# schematics.net
KiCad netlist of a schematic drawn in EAGLE
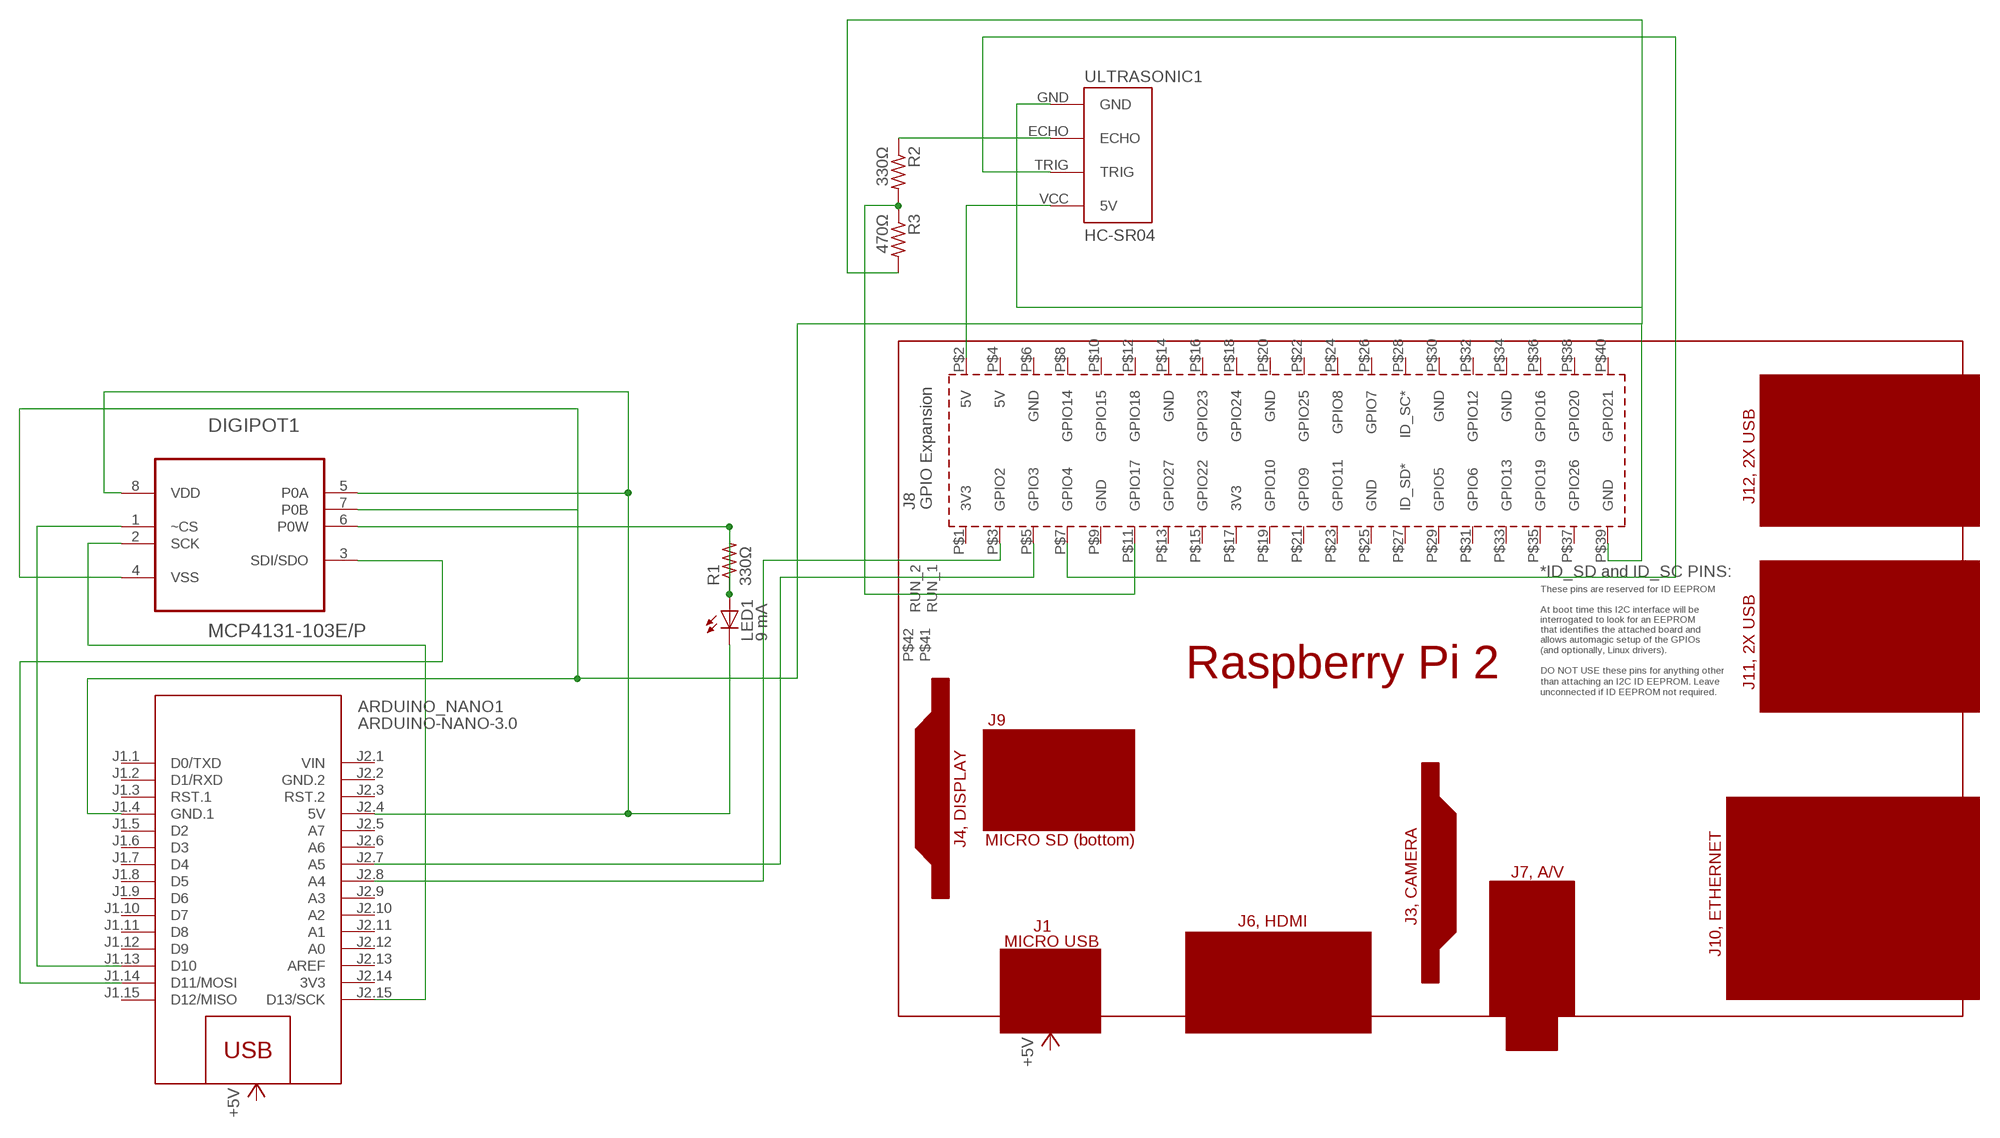
[diagram p0: schematic, sheet 1]

(export (version "E")
  (design (tool "Eeschema 10.0.6"))
  (components
    (comp (ref "ARDUINO_NANO1")
      (value "ARDUINO-NANO-3.0")
      (footprint "eagle-import:ARDUINO-NANO-3.0")
      (libsource (lib "eagle-import") (part "ARDUINO-NANO-3.0"))
    )
    (comp (ref "DIGIPOT1")
      (value "MCP4131-103E/P")
      (footprint "eagle-import:DIP254P762X533-8")
      (libsource (lib "eagle-import") (part "MCP4131-103E/P"))
    )
    (comp (ref "LED1")
      (value "9 mA")
      (footprint "eagle-import:SMARTLED-TTW")
      (libsource (lib "eagle-import") (part "LED"))
    )
    (comp (ref "R1")
      (value "330Ω")
      (footprint "eagle-import:0207_10")
      (libsource (lib "eagle-import") (part "R-US_0207/10"))
    )
    (comp (ref "R2")
      (value "330Ω")
      (footprint "eagle-import:0204_7")
      (libsource (lib "eagle-import") (part "R-US_0204/7"))
    )
    (comp (ref "R3")
      (value "470Ω")
      (footprint "eagle-import:0204_7")
      (libsource (lib "eagle-import") (part "R-US_0204/7"))
    )
    (comp (ref "RASPBERRY_PI_TWO1")
      (value "RPI2")
      (footprint "eagle-import:RPI2")
      (libsource (lib "eagle-import") (part "RPI2"))
    )
    (comp (ref "ULTRASONIC1")
      (value "HC-SR04")
      (footprint "eagle-import:HC-SR04_FOOTPRINT")
      (libsource (lib "eagle-import") (part "HC-SR04"))
    )
  )
  (nets
    (net (code "2") (name "/3V3") (class "Default")
      (node (ref "ARDUINO_NANO1") (pin "J2.14") (pinfunction "3V3_J2.14") (pintype "power_in"))
    )
    (net (code "3") (name "/GND.2") (class "Default")
      (node (ref "ARDUINO_NANO1") (pin "J2.2") (pinfunction "GND.2_J2.2") (pintype "power_in"))
    )
    (net (code "4") (name "/VIN") (class "Default")
      (node (ref "ARDUINO_NANO1") (pin "J2.1") (pinfunction "VIN_J2.1") (pintype "power_in"))
    )
    (net (code "5") (name "Net-(ARDUINO_NANO1-5V)") (class "Default")
      (node (ref "ARDUINO_NANO1") (pin "J2.4") (pinfunction "5V_J2.4") (pintype "power_in"))
      (node (ref "DIGIPOT1") (pin "5") (pinfunction "P0A_5") (pintype "bidirectional"))
      (node (ref "DIGIPOT1") (pin "8") (pinfunction "VDD_8") (pintype "power_in"))
      (node (ref "LED1") (pin "C@1") (pinfunction "C_C@1") (pintype "passive"))
    )
    (net (code "6") (name "Net-(ARDUINO_NANO1-A4)") (class "Default")
      (node (ref "ARDUINO_NANO1") (pin "J2.8") (pinfunction "A4_J2.8") (pintype "bidirectional"))
      (node (ref "RASPBERRY_PI_TWO1") (pin "P$3") (pinfunction "GPIO2_P$3") (pintype "bidirectional"))
    )
    (net (code "7") (name "Net-(ARDUINO_NANO1-A5)") (class "Default")
      (node (ref "ARDUINO_NANO1") (pin "J2.7") (pinfunction "A5_J2.7") (pintype "bidirectional"))
      (node (ref "RASPBERRY_PI_TWO1") (pin "P$5") (pinfunction "GPIO3_P$5") (pintype "bidirectional"))
    )
    (net (code "8") (name "Net-(ARDUINO_NANO1-D10)") (class "Default")
      (node (ref "ARDUINO_NANO1") (pin "J1.13") (pinfunction "D10_J1.13") (pintype "bidirectional"))
      (node (ref "DIGIPOT1") (pin "1") (pinfunction "~{CS}_1") (pintype "input"))
    )
    (net (code "9") (name "Net-(ARDUINO_NANO1-D11{slash}MOSI)") (class "Default")
      (node (ref "ARDUINO_NANO1") (pin "J1.14") (pinfunction "D11/MOSI_J1.14") (pintype "bidirectional"))
      (node (ref "DIGIPOT1") (pin "3") (pinfunction "SDI/SDO_3") (pintype "bidirectional"))
    )
    (net (code "10") (name "Net-(ARDUINO_NANO1-D13{slash}SCK)") (class "Default")
      (node (ref "ARDUINO_NANO1") (pin "J2.15") (pinfunction "D13/SCK_J2.15") (pintype "bidirectional"))
      (node (ref "DIGIPOT1") (pin "2") (pinfunction "SCK_2") (pintype "input"))
    )
    (net (code "11") (name "Net-(ARDUINO_NANO1-GND.1)") (class "Default")
      (node (ref "ARDUINO_NANO1") (pin "J1.4") (pinfunction "GND.1_J1.4") (pintype "power_in"))
      (node (ref "DIGIPOT1") (pin "4") (pinfunction "VSS_4") (pintype "power_in"))
      (node (ref "DIGIPOT1") (pin "7") (pinfunction "P0B_7") (pintype "bidirectional"))
      (node (ref "R3") (pin "2") (pinfunction "2_2") (pintype "passive"))
      (node (ref "RASPBERRY_PI_TWO1") (pin "P$39") (pinfunction "GND_P$39") (pintype "bidirectional"))
      (node (ref "ULTRASONIC1") (pin "GND") (pinfunction "GND_GND") (pintype "bidirectional"))
    )
    (net (code "12") (name "Net-(DIGIPOT1-P0W)") (class "Default")
      (node (ref "DIGIPOT1") (pin "6") (pinfunction "P0W_6") (pintype "bidirectional"))
      (node (ref "LED1") (pin "A@1") (pinfunction "A_A@1") (pintype "passive"))
      (node (ref "R1") (pin "1") (pinfunction "1_1") (pintype "passive"))
      (node (ref "R1") (pin "2") (pinfunction "2_2") (pintype "passive"))
    )
    (net (code "13") (name "Net-(R2-Pad1)") (class "Default")
      (node (ref "R2") (pin "1") (pinfunction "1_1") (pintype "passive"))
      (node (ref "ULTRASONIC1") (pin "ECHO") (pinfunction "ECHO_ECHO") (pintype "bidirectional"))
    )
    (net (code "14") (name "Net-(RASPBERRY_PI_TWO1-GPIO4)") (class "Default")
      (node (ref "RASPBERRY_PI_TWO1") (pin "P$7") (pinfunction "GPIO4_P$7") (pintype "bidirectional"))
      (node (ref "ULTRASONIC1") (pin "TRIG") (pinfunction "TRIG_TRIG") (pintype "bidirectional"))
    )
    (net (code "15") (name "Net-(RASPBERRY_PI_TWO1-GPIO17)") (class "Default")
      (node (ref "R2") (pin "2") (pinfunction "2_2") (pintype "passive"))
      (node (ref "R3") (pin "1") (pinfunction "1_1") (pintype "passive"))
      (node (ref "RASPBERRY_PI_TWO1") (pin "P$11") (pinfunction "GPIO17_P$11") (pintype "bidirectional"))
    )
    (net (code "16") (name "Net-(ULTRASONIC1-5V)") (class "Default")
      (node (ref "RASPBERRY_PI_TWO1") (pin "P$2") (pinfunction "5V_P$2") (pintype "bidirectional"))
      (node (ref "ULTRASONIC1") (pin "VCC") (pinfunction "5V_VCC") (pintype "bidirectional"))
    )
    (net (code "17") (name "unconnected-(ARDUINO_NANO1-A0-PadJ2.12)") (class "Default")
      (node (ref "ARDUINO_NANO1") (pin "J2.12") (pinfunction "A0_J2.12") (pintype "bidirectional"))
    )
    (net (code "18") (name "unconnected-(ARDUINO_NANO1-A1-PadJ2.11)") (class "Default")
      (node (ref "ARDUINO_NANO1") (pin "J2.11") (pinfunction "A1_J2.11") (pintype "bidirectional"))
    )
    (net (code "19") (name "unconnected-(ARDUINO_NANO1-A2-PadJ2.10)") (class "Default")
      (node (ref "ARDUINO_NANO1") (pin "J2.10") (pinfunction "A2_J2.10") (pintype "bidirectional"))
    )
    (net (code "20") (name "unconnected-(ARDUINO_NANO1-A3-PadJ2.9)") (class "Default")
      (node (ref "ARDUINO_NANO1") (pin "J2.9") (pinfunction "A3_J2.9") (pintype "bidirectional"))
    )
    (net (code "21") (name "unconnected-(ARDUINO_NANO1-A6-PadJ2.6)") (class "Default")
      (node (ref "ARDUINO_NANO1") (pin "J2.6") (pinfunction "A6_J2.6") (pintype "bidirectional"))
    )
    (net (code "22") (name "unconnected-(ARDUINO_NANO1-A7-PadJ2.5)") (class "Default")
      (node (ref "ARDUINO_NANO1") (pin "J2.5") (pinfunction "A7_J2.5") (pintype "bidirectional"))
    )
    (net (code "23") (name "unconnected-(ARDUINO_NANO1-AREF-PadJ2.13)") (class "Default")
      (node (ref "ARDUINO_NANO1") (pin "J2.13") (pinfunction "AREF_J2.13") (pintype "bidirectional"))
    )
    (net (code "24") (name "unconnected-(ARDUINO_NANO1-D0{slash}TXD-PadJ1.1)") (class "Default")
      (node (ref "ARDUINO_NANO1") (pin "J1.1") (pinfunction "D0/TXD_J1.1") (pintype "bidirectional"))
    )
    (net (code "25") (name "unconnected-(ARDUINO_NANO1-D1{slash}RXD-PadJ1.2)") (class "Default")
      (node (ref "ARDUINO_NANO1") (pin "J1.2") (pinfunction "D1/RXD_J1.2") (pintype "bidirectional"))
    )
    (net (code "26") (name "unconnected-(ARDUINO_NANO1-D2-PadJ1.5)") (class "Default")
      (node (ref "ARDUINO_NANO1") (pin "J1.5") (pinfunction "D2_J1.5") (pintype "bidirectional"))
    )
    (net (code "27") (name "unconnected-(ARDUINO_NANO1-D3-PadJ1.6)") (class "Default")
      (node (ref "ARDUINO_NANO1") (pin "J1.6") (pinfunction "D3_J1.6") (pintype "bidirectional"))
    )
    (net (code "28") (name "unconnected-(ARDUINO_NANO1-D4-PadJ1.7)") (class "Default")
      (node (ref "ARDUINO_NANO1") (pin "J1.7") (pinfunction "D4_J1.7") (pintype "bidirectional"))
    )
    (net (code "29") (name "unconnected-(ARDUINO_NANO1-D5-PadJ1.8)") (class "Default")
      (node (ref "ARDUINO_NANO1") (pin "J1.8") (pinfunction "D5_J1.8") (pintype "bidirectional"))
    )
    (net (code "30") (name "unconnected-(ARDUINO_NANO1-D6-PadJ1.9)") (class "Default")
      (node (ref "ARDUINO_NANO1") (pin "J1.9") (pinfunction "D6_J1.9") (pintype "bidirectional"))
    )
    (net (code "31") (name "unconnected-(ARDUINO_NANO1-D7-PadJ1.10)") (class "Default")
      (node (ref "ARDUINO_NANO1") (pin "J1.10") (pinfunction "D7_J1.10") (pintype "bidirectional"))
    )
    (net (code "32") (name "unconnected-(ARDUINO_NANO1-D8-PadJ1.11)") (class "Default")
      (node (ref "ARDUINO_NANO1") (pin "J1.11") (pinfunction "D8_J1.11") (pintype "bidirectional"))
    )
    (net (code "33") (name "unconnected-(ARDUINO_NANO1-D9-PadJ1.12)") (class "Default")
      (node (ref "ARDUINO_NANO1") (pin "J1.12") (pinfunction "D9_J1.12") (pintype "bidirectional"))
    )
    (net (code "34") (name "unconnected-(ARDUINO_NANO1-D12{slash}MISO-PadJ1.15)") (class "Default")
      (node (ref "ARDUINO_NANO1") (pin "J1.15") (pinfunction "D12/MISO_J1.15") (pintype "bidirectional"))
    )
    (net (code "35") (name "unconnected-(ARDUINO_NANO1-RST.1-PadJ1.3)") (class "Default")
      (node (ref "ARDUINO_NANO1") (pin "J1.3") (pinfunction "RST.1_J1.3") (pintype "bidirectional"))
    )
    (net (code "36") (name "unconnected-(ARDUINO_NANO1-RST.2-PadJ2.3)") (class "Default")
      (node (ref "ARDUINO_NANO1") (pin "J2.3") (pinfunction "RST.2_J2.3") (pintype "bidirectional"))
    )
    (net (code "37") (name "unconnected-(RASPBERRY_PI_TWO1-3V3-PadP$1)") (class "Default")
      (node (ref "RASPBERRY_PI_TWO1") (pin "P$1") (pinfunction "3V3_P$1") (pintype "bidirectional"))
    )
    (net (code "38") (name "unconnected-(RASPBERRY_PI_TWO1-3V3-PadP$17)") (class "Default")
      (node (ref "RASPBERRY_PI_TWO1") (pin "P$17") (pinfunction "3V3_P$17") (pintype "bidirectional"))
    )
    (net (code "39") (name "unconnected-(RASPBERRY_PI_TWO1-5V-PadP$4)") (class "Default")
      (node (ref "RASPBERRY_PI_TWO1") (pin "P$4") (pinfunction "5V_P$4") (pintype "bidirectional"))
    )
    (net (code "40") (name "unconnected-(RASPBERRY_PI_TWO1-GND-PadP$6)") (class "Default")
      (node (ref "RASPBERRY_PI_TWO1") (pin "P$6") (pinfunction "GND_P$6") (pintype "bidirectional"))
    )
    (net (code "41") (name "unconnected-(RASPBERRY_PI_TWO1-GND-PadP$9)") (class "Default")
      (node (ref "RASPBERRY_PI_TWO1") (pin "P$9") (pinfunction "GND_P$9") (pintype "bidirectional"))
    )
    (net (code "42") (name "unconnected-(RASPBERRY_PI_TWO1-GND-PadP$14)") (class "Default")
      (node (ref "RASPBERRY_PI_TWO1") (pin "P$14") (pinfunction "GND_P$14") (pintype "bidirectional"))
    )
    (net (code "43") (name "unconnected-(RASPBERRY_PI_TWO1-GND-PadP$20)") (class "Default")
      (node (ref "RASPBERRY_PI_TWO1") (pin "P$20") (pinfunction "GND_P$20") (pintype "bidirectional"))
    )
    (net (code "44") (name "unconnected-(RASPBERRY_PI_TWO1-GND-PadP$25)") (class "Default")
      (node (ref "RASPBERRY_PI_TWO1") (pin "P$25") (pinfunction "GND_P$25") (pintype "bidirectional"))
    )
    (net (code "45") (name "unconnected-(RASPBERRY_PI_TWO1-GND-PadP$30)") (class "Default")
      (node (ref "RASPBERRY_PI_TWO1") (pin "P$30") (pinfunction "GND_P$30") (pintype "bidirectional"))
    )
    (net (code "46") (name "unconnected-(RASPBERRY_PI_TWO1-GND-PadP$34)") (class "Default")
      (node (ref "RASPBERRY_PI_TWO1") (pin "P$34") (pinfunction "GND_P$34") (pintype "bidirectional"))
    )
    (net (code "47") (name "unconnected-(RASPBERRY_PI_TWO1-GPIO5-PadP$29)") (class "Default")
      (node (ref "RASPBERRY_PI_TWO1") (pin "P$29") (pinfunction "GPIO5_P$29") (pintype "bidirectional"))
    )
    (net (code "48") (name "unconnected-(RASPBERRY_PI_TWO1-GPIO6-PadP$31)") (class "Default")
      (node (ref "RASPBERRY_PI_TWO1") (pin "P$31") (pinfunction "GPIO6_P$31") (pintype "bidirectional"))
    )
    (net (code "49") (name "unconnected-(RASPBERRY_PI_TWO1-GPIO7-PadP$26)") (class "Default")
      (node (ref "RASPBERRY_PI_TWO1") (pin "P$26") (pinfunction "GPIO7_P$26") (pintype "bidirectional"))
    )
    (net (code "50") (name "unconnected-(RASPBERRY_PI_TWO1-GPIO8-PadP$24)") (class "Default")
      (node (ref "RASPBERRY_PI_TWO1") (pin "P$24") (pinfunction "GPIO8_P$24") (pintype "bidirectional"))
    )
    (net (code "51") (name "unconnected-(RASPBERRY_PI_TWO1-GPIO9-PadP$21)") (class "Default")
      (node (ref "RASPBERRY_PI_TWO1") (pin "P$21") (pinfunction "GPIO9_P$21") (pintype "bidirectional"))
    )
    (net (code "52") (name "unconnected-(RASPBERRY_PI_TWO1-GPIO10-PadP$19)") (class "Default")
      (node (ref "RASPBERRY_PI_TWO1") (pin "P$19") (pinfunction "GPIO10_P$19") (pintype "bidirectional"))
    )
    (net (code "53") (name "unconnected-(RASPBERRY_PI_TWO1-GPIO11-PadP$23)") (class "Default")
      (node (ref "RASPBERRY_PI_TWO1") (pin "P$23") (pinfunction "GPIO11_P$23") (pintype "bidirectional"))
    )
    (net (code "54") (name "unconnected-(RASPBERRY_PI_TWO1-GPIO12-PadP$32)") (class "Default")
      (node (ref "RASPBERRY_PI_TWO1") (pin "P$32") (pinfunction "GPIO12_P$32") (pintype "bidirectional"))
    )
    (net (code "55") (name "unconnected-(RASPBERRY_PI_TWO1-GPIO13-PadP$33)") (class "Default")
      (node (ref "RASPBERRY_PI_TWO1") (pin "P$33") (pinfunction "GPIO13_P$33") (pintype "bidirectional"))
    )
    (net (code "56") (name "unconnected-(RASPBERRY_PI_TWO1-GPIO14-PadP$8)") (class "Default")
      (node (ref "RASPBERRY_PI_TWO1") (pin "P$8") (pinfunction "GPIO14_P$8") (pintype "bidirectional"))
    )
    (net (code "57") (name "unconnected-(RASPBERRY_PI_TWO1-GPIO15-PadP$10)") (class "Default")
      (node (ref "RASPBERRY_PI_TWO1") (pin "P$10") (pinfunction "GPIO15_P$10") (pintype "bidirectional"))
    )
    (net (code "58") (name "unconnected-(RASPBERRY_PI_TWO1-GPIO16-PadP$36)") (class "Default")
      (node (ref "RASPBERRY_PI_TWO1") (pin "P$36") (pinfunction "GPIO16_P$36") (pintype "bidirectional"))
    )
    (net (code "59") (name "unconnected-(RASPBERRY_PI_TWO1-GPIO18-PadP$12)") (class "Default")
      (node (ref "RASPBERRY_PI_TWO1") (pin "P$12") (pinfunction "GPIO18_P$12") (pintype "bidirectional"))
    )
    (net (code "60") (name "unconnected-(RASPBERRY_PI_TWO1-GPIO19-PadP$35)") (class "Default")
      (node (ref "RASPBERRY_PI_TWO1") (pin "P$35") (pinfunction "GPIO19_P$35") (pintype "bidirectional"))
    )
    (net (code "61") (name "unconnected-(RASPBERRY_PI_TWO1-GPIO20-PadP$38)") (class "Default")
      (node (ref "RASPBERRY_PI_TWO1") (pin "P$38") (pinfunction "GPIO20_P$38") (pintype "bidirectional"))
    )
    (net (code "62") (name "unconnected-(RASPBERRY_PI_TWO1-GPIO21-PadP$40)") (class "Default")
      (node (ref "RASPBERRY_PI_TWO1") (pin "P$40") (pinfunction "GPIO21_P$40") (pintype "bidirectional"))
    )
    (net (code "63") (name "unconnected-(RASPBERRY_PI_TWO1-GPIO22-PadP$15)") (class "Default")
      (node (ref "RASPBERRY_PI_TWO1") (pin "P$15") (pinfunction "GPIO22_P$15") (pintype "bidirectional"))
    )
    (net (code "64") (name "unconnected-(RASPBERRY_PI_TWO1-GPIO23-PadP$16)") (class "Default")
      (node (ref "RASPBERRY_PI_TWO1") (pin "P$16") (pinfunction "GPIO23_P$16") (pintype "bidirectional"))
    )
    (net (code "65") (name "unconnected-(RASPBERRY_PI_TWO1-GPIO24-PadP$18)") (class "Default")
      (node (ref "RASPBERRY_PI_TWO1") (pin "P$18") (pinfunction "GPIO24_P$18") (pintype "bidirectional"))
    )
    (net (code "66") (name "unconnected-(RASPBERRY_PI_TWO1-GPIO25-PadP$22)") (class "Default")
      (node (ref "RASPBERRY_PI_TWO1") (pin "P$22") (pinfunction "GPIO25_P$22") (pintype "bidirectional"))
    )
    (net (code "67") (name "unconnected-(RASPBERRY_PI_TWO1-GPIO26-PadP$37)") (class "Default")
      (node (ref "RASPBERRY_PI_TWO1") (pin "P$37") (pinfunction "GPIO26_P$37") (pintype "bidirectional"))
    )
    (net (code "68") (name "unconnected-(RASPBERRY_PI_TWO1-GPIO27-PadP$13)") (class "Default")
      (node (ref "RASPBERRY_PI_TWO1") (pin "P$13") (pinfunction "GPIO27_P$13") (pintype "bidirectional"))
    )
    (net (code "69") (name "unconnected-(RASPBERRY_PI_TWO1-ID_SC*-PadP$28)") (class "Default")
      (node (ref "RASPBERRY_PI_TWO1") (pin "P$28") (pinfunction "ID_SC*_P$28") (pintype "bidirectional"))
    )
    (net (code "70") (name "unconnected-(RASPBERRY_PI_TWO1-ID_SD*-PadP$27)") (class "Default")
      (node (ref "RASPBERRY_PI_TWO1") (pin "P$27") (pinfunction "ID_SD*_P$27") (pintype "bidirectional"))
    )
    (net (code "71") (name "unconnected-(RASPBERRY_PI_TWO1-RUN_1-PadP$41)") (class "Default")
      (node (ref "RASPBERRY_PI_TWO1") (pin "P$41") (pinfunction "RUN_1_P$41") (pintype "bidirectional"))
    )
    (net (code "72") (name "unconnected-(RASPBERRY_PI_TWO1-RUN_2-PadP$42)") (class "Default")
      (node (ref "RASPBERRY_PI_TWO1") (pin "P$42") (pinfunction "RUN_2_P$42") (pintype "bidirectional"))
    )
  )
)
